# connectors.net
KiCad netlist of a schematic drawn in Altium Designer
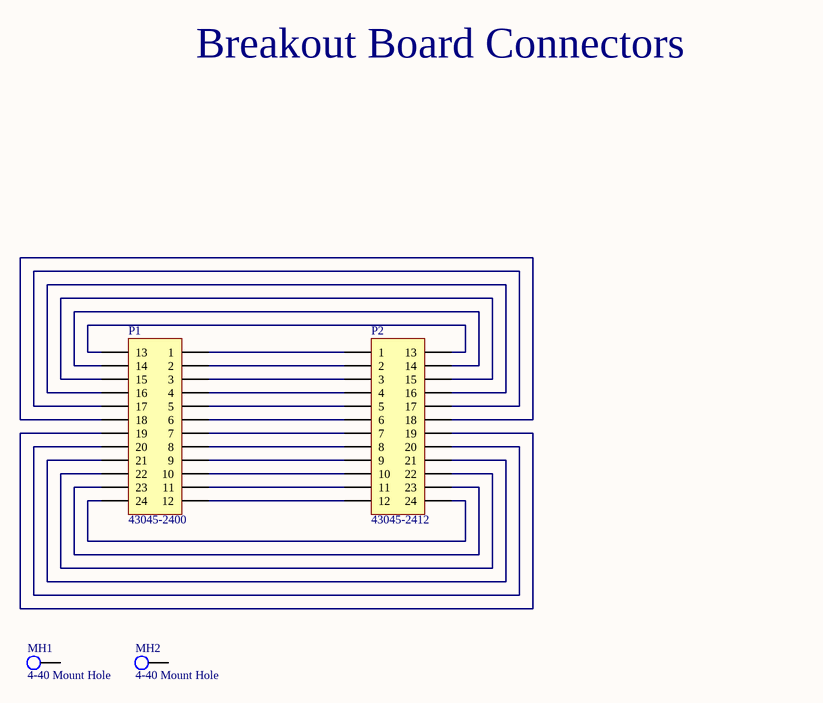
[diagram p0: connectors.SchDoc]

(export (version "E")
  (design (tool "Eeschema 10.0.6"))
  (components
    (comp (ref "MH1")
      (value "4-40 Mount Hole")
      (footprint "MH")
      (libsource (lib "misc") (part "4-40 Mount Hole"))
    )
    (comp (ref "MH2")
      (value "4-40 Mount Hole")
      (footprint "MH")
      (libsource (lib "misc") (part "4-40 Mount Hole"))
    )
    (comp (ref "P1")
      (value "43045-2400")
      (footprint "430452400")
      (fields (field (name "MANUFACTURER") "Molex"))
      (libsource (lib "connector") (part "43045-2400"))
    )
    (comp (ref "P2")
      (value "43045-2412")
      (footprint "0430452412")
      (fields (field (name "MANUFACTURER") "Molex"))
      (libsource (lib "connector") (part "43045-2412"))
    )
  )
  (nets
    (net (code "1") (name "Net-(P1-Pad1)") (class "Default")
      (node (ref "P1") (pin "1") (pinfunction "1_1") (pintype "passive"))
      (node (ref "P2") (pin "1") (pinfunction "1_1") (pintype "passive"))
    )
    (net (code "2") (name "Net-(P1-Pad2)") (class "Default")
      (node (ref "P1") (pin "2") (pinfunction "2_2") (pintype "passive"))
      (node (ref "P2") (pin "2") (pinfunction "2_2") (pintype "passive"))
    )
    (net (code "3") (name "Net-(P1-Pad3)") (class "Default")
      (node (ref "P1") (pin "3") (pinfunction "3_3") (pintype "passive"))
      (node (ref "P2") (pin "3") (pinfunction "3_3") (pintype "passive"))
    )
    (net (code "4") (name "Net-(P1-Pad4)") (class "Default")
      (node (ref "P1") (pin "4") (pinfunction "4_4") (pintype "passive"))
      (node (ref "P2") (pin "4") (pinfunction "4_4") (pintype "passive"))
    )
    (net (code "5") (name "Net-(P1-Pad5)") (class "Default")
      (node (ref "P1") (pin "5") (pinfunction "5_5") (pintype "passive"))
      (node (ref "P2") (pin "5") (pinfunction "5_5") (pintype "passive"))
    )
    (net (code "6") (name "Net-(P1-Pad6)") (class "Default")
      (node (ref "P1") (pin "6") (pinfunction "6_6") (pintype "passive"))
      (node (ref "P2") (pin "6") (pinfunction "6_6") (pintype "passive"))
    )
    (net (code "7") (name "Net-(P1-Pad7)") (class "Default")
      (node (ref "P1") (pin "7") (pinfunction "7_7") (pintype "passive"))
      (node (ref "P2") (pin "7") (pinfunction "7_7") (pintype "passive"))
    )
    (net (code "8") (name "Net-(P1-Pad8)") (class "Default")
      (node (ref "P1") (pin "8") (pinfunction "8_8") (pintype "passive"))
      (node (ref "P2") (pin "8") (pinfunction "8_8") (pintype "passive"))
    )
    (net (code "9") (name "Net-(P1-Pad9)") (class "Default")
      (node (ref "P1") (pin "9") (pinfunction "9_9") (pintype "passive"))
      (node (ref "P2") (pin "9") (pinfunction "9_9") (pintype "passive"))
    )
    (net (code "10") (name "Net-(P1-Pad10)") (class "Default")
      (node (ref "P1") (pin "10") (pinfunction "10_10") (pintype "passive"))
      (node (ref "P2") (pin "10") (pinfunction "10_10") (pintype "passive"))
    )
    (net (code "11") (name "Net-(P1-Pad11)") (class "Default")
      (node (ref "P1") (pin "11") (pinfunction "11_11") (pintype "passive"))
      (node (ref "P2") (pin "11") (pinfunction "11_11") (pintype "passive"))
    )
    (net (code "12") (name "Net-(P1-Pad12)") (class "Default")
      (node (ref "P1") (pin "12") (pinfunction "12_12") (pintype "passive"))
      (node (ref "P2") (pin "12") (pinfunction "12_12") (pintype "passive"))
    )
    (net (code "13") (name "Net-(P1-Pad13)") (class "Default")
      (node (ref "P1") (pin "13") (pinfunction "13_13") (pintype "passive"))
      (node (ref "P2") (pin "13") (pinfunction "13_13") (pintype "passive"))
    )
    (net (code "14") (name "Net-(P1-Pad14)") (class "Default")
      (node (ref "P1") (pin "14") (pinfunction "14_14") (pintype "passive"))
      (node (ref "P2") (pin "14") (pinfunction "14_14") (pintype "passive"))
    )
    (net (code "15") (name "Net-(P1-Pad15)") (class "Default")
      (node (ref "P1") (pin "15") (pinfunction "15_15") (pintype "passive"))
      (node (ref "P2") (pin "15") (pinfunction "15_15") (pintype "passive"))
    )
    (net (code "16") (name "Net-(P1-Pad16)") (class "Default")
      (node (ref "P1") (pin "16") (pinfunction "16_16") (pintype "passive"))
      (node (ref "P2") (pin "16") (pinfunction "16_16") (pintype "passive"))
    )
    (net (code "17") (name "Net-(P1-Pad17)") (class "Default")
      (node (ref "P1") (pin "17") (pinfunction "17_17") (pintype "passive"))
      (node (ref "P2") (pin "17") (pinfunction "17_17") (pintype "passive"))
    )
    (net (code "18") (name "Net-(P1-Pad18)") (class "Default")
      (node (ref "P1") (pin "18") (pinfunction "18_18") (pintype "passive"))
      (node (ref "P2") (pin "18") (pinfunction "18_18") (pintype "passive"))
    )
    (net (code "19") (name "Net-(P1-Pad19)") (class "Default")
      (node (ref "P1") (pin "19") (pinfunction "19_19") (pintype "passive"))
      (node (ref "P2") (pin "19") (pinfunction "19_19") (pintype "passive"))
    )
    (net (code "20") (name "Net-(P1-Pad20)") (class "Default")
      (node (ref "P1") (pin "20") (pinfunction "20_20") (pintype "passive"))
      (node (ref "P2") (pin "20") (pinfunction "20_20") (pintype "passive"))
    )
    (net (code "21") (name "Net-(P1-Pad21)") (class "Default")
      (node (ref "P1") (pin "21") (pinfunction "21_21") (pintype "passive"))
      (node (ref "P2") (pin "21") (pinfunction "21_21") (pintype "passive"))
    )
    (net (code "22") (name "Net-(P1-Pad22)") (class "Default")
      (node (ref "P1") (pin "22") (pinfunction "22_22") (pintype "passive"))
      (node (ref "P2") (pin "22") (pinfunction "22_22") (pintype "passive"))
    )
    (net (code "23") (name "Net-(P1-Pad23)") (class "Default")
      (node (ref "P1") (pin "23") (pinfunction "23_23") (pintype "passive"))
      (node (ref "P2") (pin "23") (pinfunction "23_23") (pintype "passive"))
    )
    (net (code "24") (name "Net-(P1-Pad24)") (class "Default")
      (node (ref "P1") (pin "24") (pinfunction "24_24") (pintype "passive"))
      (node (ref "P2") (pin "24") (pinfunction "24_24") (pintype "passive"))
    )
    (net (code "25") (name "unconnected-(MH1-Pad46)") (class "Default")
      (node (ref "MH1") (pin "46") (pinfunction "46_46") (pintype "passive"))
    )
    (net (code "26") (name "unconnected-(MH2-Pad46)") (class "Default")
      (node (ref "MH2") (pin "46") (pinfunction "46_46") (pintype "passive"))
    )
  )
)
